# PANUmbRev2.net
KiCad netlist of a schematic drawn in Altium Designer
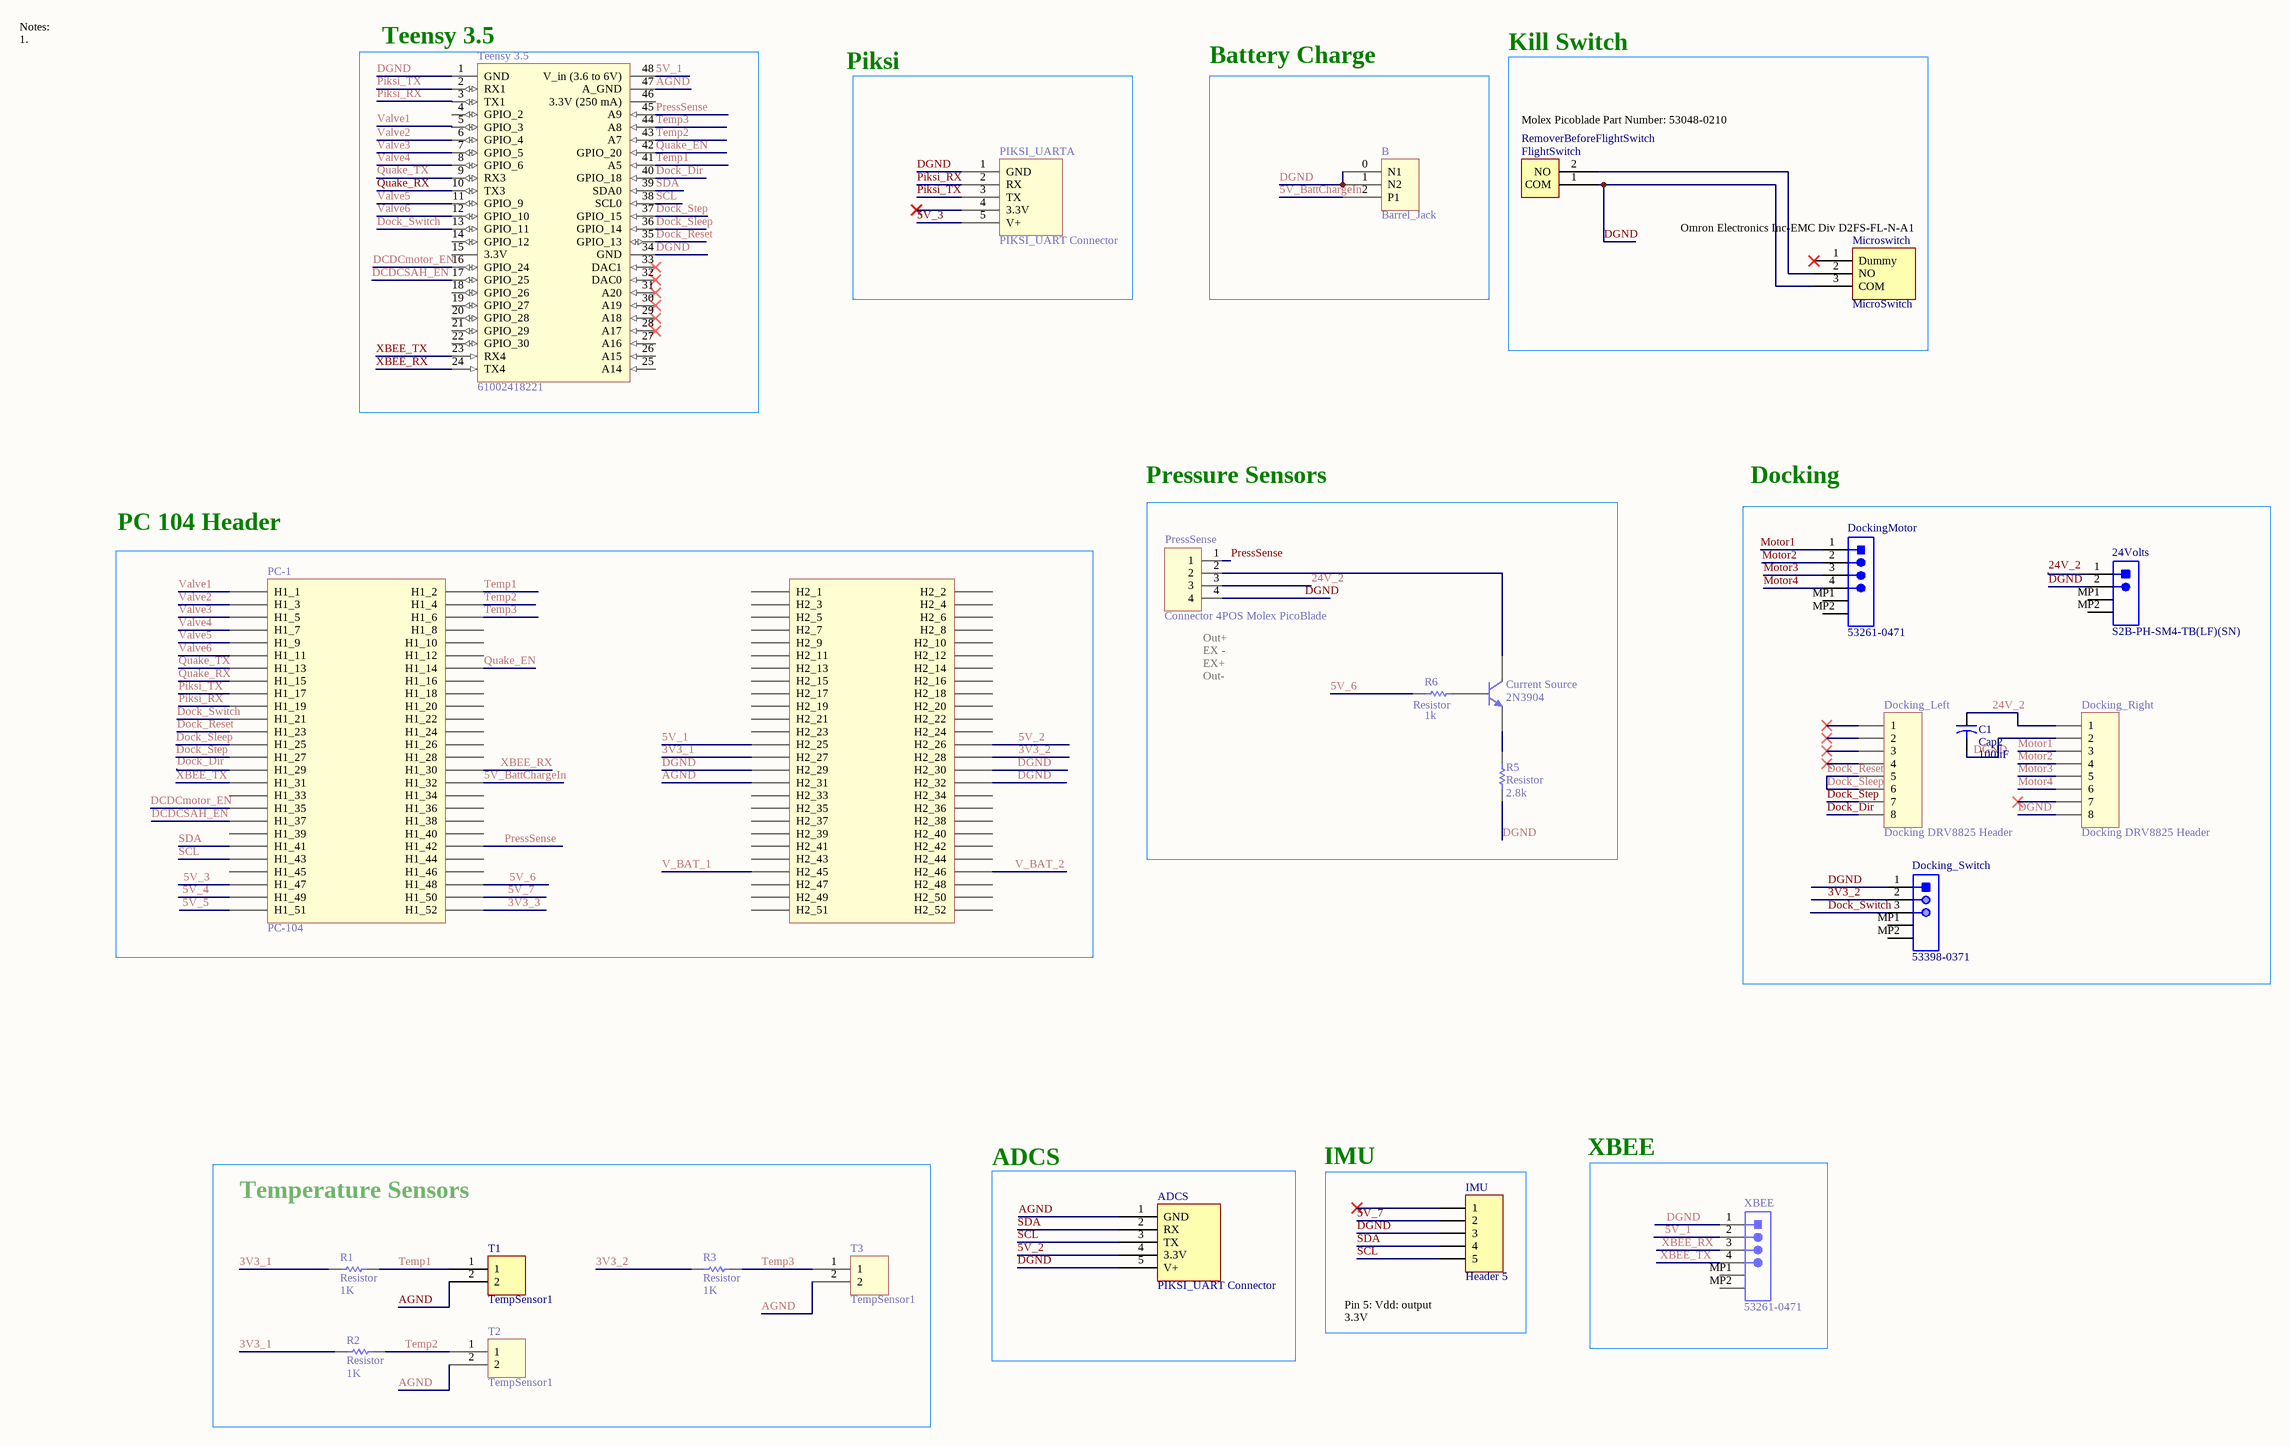
[diagram p0: PANUmbRev2.SchDoc]

(export (version "E")
  (design (tool "Eeschema 10.0.6"))
  (components
    (comp (ref "24Volts")
      (value "S2B-PH-SM4-TB(LF)(SN)")
      (footprint "JST- S2B-PH-SM4-TB(LF)(SN)-2_V")
      (description "Male Header, Pitch 2 mm, 1 x 2 Position, Height 5.5 mm, -25 to 85 degC, RoHS, Tape and Reel")
      (libsource (lib "Altium Content Vault") (part "CN-1P-2M-R2"))
    )
    (comp (ref "ADCS")
      (value "PIKSI_UART Connector")
      (footprint "UmbilicalConnectors:Molex Picoblade 5 Pin")
      (description "Molex Picoblade 53261-0571")
      (libsource (lib "UmbilicalBoardV2") (part "PIKSI_UART Connector"))
    )
    (comp (ref "B")
      (value "Barrel_Jack")
      (footprint "UmbilicalConnectors:Barrel_Jack")
      (libsource (lib "UmbilicalBoardV2") (part "Barrel_Jack"))
    )
    (comp (ref "C1")
      (value "Cap2")
      (footprint "CAPR5-4X5")
      (description "Capacitor")
      (fields (field (name "ALTIUM_VALUE") "100uF") (field (name "PUBLISHER") "Altium Limited"))
      (libsource (lib "Miscellaneous Devices") (part "Cap2"))
    )
    (comp (ref "Current Source")
      (value "2N3904")
      (footprint "TO-92A")
      (description "NPN General Purpose Amplifier")
      (fields (field (name "PUBLISHER") "Altium Limited"))
      (libsource (lib "Miscellaneous Devices") (part "2N3904"))
    )
    (comp (ref "DockingMotor")
      (value "53261-0471")
      (footprint "MOLEX-53261-0471_V")
      (description "Male Header, Pitch 1.25 mm, 1 x 4 Position, Height 3.4 mm, -40 to 85 degC, RoHS, Tape and Reel")
      (fields (field (name "MANUFACTURER") "Molex"))
      (libsource (lib "Altium Content Vault") (part "CN-1P-2M-R4_A"))
    )
    (comp (ref "Docking_Left")
      (value "Docking DRV8825 Header")
      (footprint "HDR1X8")
      (description "Header, 8-Pin")
      (fields (field (name "PUBLISHER") "Altium Limited"))
      (libsource (lib "Miscellaneous Connectors") (part "Header 8"))
    )
    (comp (ref "Docking_Right")
      (value "Docking DRV8825 Header")
      (footprint "HDR1X8")
      (description "Header, 8-Pin")
      (fields (field (name "PUBLISHER") "Altium Limited"))
      (libsource (lib "Miscellaneous Connectors") (part "Header 8"))
    )
    (comp (ref "Docking_Switch")
      (value "53398-0371")
      (footprint "MOLX-53398-0371_V")
      (description "Male Header, Pitch 1.25 mm, 1 x 3 Position, Height 4.7 mm, -40 to 85 degC, RoHS, Tape and Reel")
      (fields (field (name "MANUFACTURER") "Molex"))
      (libsource (lib "Altium Content Vault") (part "CN-1P-2M-R3"))
    )
    (comp (ref "FlightSwitch")
      (value "RemoverBeforeFlightSwitch")
      (footprint "UmbilicalConnectors:RemoverBeforeFlight Switch")
      (description "53048-0210 Molex Picoblade")
      (libsource (lib "") (part "RemoverBeforeFlightSwitch_1"))
    )
    (comp (ref "IMU")
      (value "Header 5")
      (footprint "HDR1X5")
      (description "Header, 5-Pin")
      (fields (field (name "PUBLISHER") "Altium Limited"))
      (libsource (lib "Miscellaneous Connectors") (part "Header 5"))
    )
    (comp (ref "Microswitch")
      (value "MicroSwitch")
      (footprint "UmbilicalConnectors:MicroSwitch_3pin")
      (description "Omron Electronics Inc-EMC Div D2FS-FL-N-A1")
      (libsource (lib "UmbilicalBoardV2") (part "MicroSwitch"))
    )
    (comp (ref "PC-1")
      (value "PC-104")
      (footprint "PC-104FOOTPRINT")
      (description "ESQ-126-14-G-D (2 total needed)")
      (libsource (lib "AdapterBoard") (part "PC-104"))
    )
    (comp (ref "PIKSI_UARTA")
      (value "PIKSI_UART Connector")
      (footprint "UmbilicalConnectors:Molex Picoblade 5 Pin")
      (description "Molex Picoblade 53261-0571")
      (libsource (lib "UmbilicalBoardV2") (part "PIKSI_UART Connector"))
    )
    (comp (ref "PressSense")
      (value "Connector 4POS Molex PicoBlade")
      (footprint "532610471")
      (libsource (lib "SchematicComponents") (part "532610471"))
    )
    (comp (ref "R1")
      (value "Resistor")
      (footprint "AXIAL-0.3")
      (fields (field (name "ALTIUM_VALUE") "1K") (field (name "PUBLISHER") "Altium Limited"))
      (libsource (lib "Miscellaneous Devices") (part "Res1"))
    )
    (comp (ref "R2")
      (value "Resistor")
      (footprint "AXIAL-0.3")
      (fields (field (name "ALTIUM_VALUE") "1K") (field (name "PUBLISHER") "Altium Limited"))
      (libsource (lib "Miscellaneous Devices") (part "Res1"))
    )
    (comp (ref "R3")
      (value "Resistor")
      (footprint "AXIAL-0.3")
      (fields (field (name "ALTIUM_VALUE") "1K") (field (name "PUBLISHER") "Altium Limited"))
      (libsource (lib "Miscellaneous Devices") (part "Res1"))
    )
    (comp (ref "R5")
      (value "Resistor")
      (footprint "AXIAL-0.3")
      (fields (field (name "ALTIUM_VALUE") "2.8k") (field (name "PUBLISHER") "Altium Limited"))
      (libsource (lib "Miscellaneous Devices") (part "Res1"))
    )
    (comp (ref "R6")
      (value "Resistor")
      (footprint "AXIAL-0.3")
      (fields (field (name "ALTIUM_VALUE") "1k") (field (name "PUBLISHER") "Altium Limited"))
      (libsource (lib "Miscellaneous Devices") (part "Res1"))
    )
    (comp (ref "T1")
      (value "TempSensor1")
      (footprint "UmbilicalConnectors:RemoverBeforeFlight Switch")
      (description "53048-0210 Molex Picoblade")
      (libsource (lib "UmbilicalBoardV2") (part "RemoverBeforeFlightSwitch"))
    )
    (comp (ref "T2")
      (value "TempSensor1")
      (footprint "UmbilicalConnectors:RemoverBeforeFlight Switch")
      (description "53048-0210 Molex Picoblade")
      (libsource (lib "UmbilicalBoardV2") (part "RemoverBeforeFlightSwitch"))
    )
    (comp (ref "T3")
      (value "TempSensor1")
      (footprint "UmbilicalConnectors:RemoverBeforeFlight Switch")
      (description "53048-0210 Molex Picoblade")
      (libsource (lib "UmbilicalBoardV2") (part "RemoverBeforeFlightSwitch"))
    )
    (comp (ref "Teensy 3.5")
      (value "61002418221")
      (footprint "61002418221")
      (fields (field (name "RS PART NUMBER") "1216841"))
      (libsource (lib "Teensy 3-5 24POS 2ROW SMD") (part "61002418221"))
    )
    (comp (ref "XBEE")
      (value "53261-0471")
      (footprint "MOLEX-53261-0471_V")
      (description "Male Header, Pitch 1.25 mm, 1 x 4 Position, Height 3.4 mm, -40 to 85 degC, RoHS, Tape and Reel")
      (fields (field (name "MANUFACTURER") "Molex"))
      (libsource (lib "Altium Content Vault") (part "CMP-2000-05238-1"))
    )
  )
  (nets
    (net (code "1") (name "/3V3_1") (class "Default")
      (node (ref "PC-1") (pin "H2_27") (pinfunction "H2_27_H2_27") (pintype "passive"))
      (node (ref "R1") (pin "1") (pinfunction "1_1") (pintype "passive"))
      (node (ref "R2") (pin "1") (pinfunction "1_1") (pintype "passive"))
    )
    (net (code "2") (name "/3V3_2") (class "Default")
      (node (ref "Docking_Switch") (pin "2") (pinfunction "2_2") (pintype "passive"))
      (node (ref "PC-1") (pin "H2_28") (pinfunction "H2_28_H2_28") (pintype "passive"))
      (node (ref "R3") (pin "1") (pinfunction "1_1") (pintype "passive"))
    )
    (net (code "3") (name "/3V3_3") (class "Default")
      (node (ref "PC-1") (pin "H1_52") (pinfunction "H1_52_H1_52") (pintype "passive"))
    )
    (net (code "4") (name "/5V_1") (class "Default")
      (node (ref "PC-1") (pin "H2_25") (pinfunction "H2_25_H2_25") (pintype "passive"))
      (node (ref "Teensy 3.5") (pin "48") (pinfunction "V_in_(3.6_to_6V)_48") (pintype "power_in"))
      (node (ref "XBEE") (pin "2") (pinfunction "2_2") (pintype "passive"))
    )
    (net (code "5") (name "/5V_2") (class "Default")
      (node (ref "ADCS") (pin "4") (pinfunction "3.3V_4") (pintype "passive"))
      (node (ref "PC-1") (pin "H2_26") (pinfunction "H2_26_H2_26") (pintype "passive"))
    )
    (net (code "6") (name "/5V_3") (class "Default")
      (node (ref "PC-1") (pin "H1_47") (pinfunction "H1_47_H1_47") (pintype "passive"))
      (node (ref "PIKSI_UARTA") (pin "5") (pinfunction "V+_5") (pintype "passive"))
    )
    (net (code "7") (name "/5V_4") (class "Default")
      (node (ref "PC-1") (pin "H1_49") (pinfunction "H1_49_H1_49") (pintype "passive"))
    )
    (net (code "8") (name "/5V_5") (class "Default")
      (node (ref "PC-1") (pin "H1_51") (pinfunction "H1_51_H1_51") (pintype "passive"))
    )
    (net (code "9") (name "/5V_6") (class "Default")
      (node (ref "PC-1") (pin "H1_48") (pinfunction "H1_48_H1_48") (pintype "passive"))
      (node (ref "R6") (pin "2") (pinfunction "2_2") (pintype "passive"))
    )
    (net (code "10") (name "/5V_7") (class "Default")
      (node (ref "IMU") (pin "2") (pinfunction "2_2") (pintype "passive"))
      (node (ref "PC-1") (pin "H1_50") (pinfunction "H1_50_H1_50") (pintype "passive"))
    )
    (net (code "11") (name "/5V_BattChargeIn") (class "Default")
      (node (ref "B") (pin "2") (pinfunction "P1_2") (pintype "passive"))
      (node (ref "PC-1") (pin "H1_32") (pinfunction "H1_32_H1_32") (pintype "passive"))
    )
    (net (code "12") (name "/24V_2") (class "Default")
      (node (ref "24Volts") (pin "1") (pinfunction "1_1") (pintype "passive"))
      (node (ref "C1") (pin "1") (pinfunction "1_1") (pintype "passive"))
      (node (ref "Docking_Right") (pin "1") (pinfunction "1_1") (pintype "passive"))
      (node (ref "PressSense") (pin "3") (pinfunction "3_3") (pintype "passive"))
    )
    (net (code "13") (name "/AGND") (class "Default")
      (node (ref "ADCS") (pin "1") (pinfunction "GND_1") (pintype "passive"))
      (node (ref "PC-1") (pin "H2_31") (pinfunction "H2_31_H2_31") (pintype "passive"))
      (node (ref "T1") (pin "2") (pinfunction "2_2") (pintype "passive"))
      (node (ref "T2") (pin "2") (pinfunction "2_2") (pintype "passive"))
      (node (ref "T3") (pin "2") (pinfunction "2_2") (pintype "passive"))
      (node (ref "Teensy 3.5") (pin "47") (pinfunction "A_GND_47") (pintype "power_in"))
    )
    (net (code "14") (name "/DCDCSAH_EN") (class "Default")
      (node (ref "PC-1") (pin "H1_37") (pinfunction "H1_37_H1_37") (pintype "passive"))
      (node (ref "Teensy 3.5") (pin "17") (pinfunction "GPIO_25_17") (pintype "bidirectional"))
    )
    (net (code "15") (name "/DCDCmotor_EN") (class "Default")
      (node (ref "PC-1") (pin "H1_35") (pinfunction "H1_35_H1_35") (pintype "passive"))
      (node (ref "Teensy 3.5") (pin "16") (pinfunction "GPIO_24_16") (pintype "bidirectional"))
    )
    (net (code "16") (name "/DGND") (class "Default")
      (node (ref "24Volts") (pin "2") (pinfunction "2_2") (pintype "passive"))
      (node (ref "ADCS") (pin "5") (pinfunction "V+_5") (pintype "passive"))
      (node (ref "B") (pin "0") (pinfunction "N1_0") (pintype "passive"))
      (node (ref "B") (pin "1") (pinfunction "N2_1") (pintype "passive"))
      (node (ref "C1") (pin "2") (pinfunction "2_2") (pintype "passive"))
      (node (ref "Docking_Right") (pin "2") (pinfunction "2_2") (pintype "passive"))
      (node (ref "Docking_Right") (pin "8") (pinfunction "8_8") (pintype "passive"))
      (node (ref "Docking_Switch") (pin "1") (pinfunction "1_1") (pintype "passive"))
      (node (ref "FlightSwitch") (pin "1") (pinfunction "COM_1") (pintype "passive"))
      (node (ref "IMU") (pin "3") (pinfunction "3_3") (pintype "passive"))
      (node (ref "Microswitch") (pin "3") (pinfunction "COM_3") (pintype "passive"))
      (node (ref "PC-1") (pin "H2_29") (pinfunction "H2_29_H2_29") (pintype "passive"))
      (node (ref "PC-1") (pin "H2_30") (pinfunction "H2_30_H2_30") (pintype "passive"))
      (node (ref "PC-1") (pin "H2_32") (pinfunction "H2_32_H2_32") (pintype "passive"))
      (node (ref "PIKSI_UARTA") (pin "1") (pinfunction "GND_1") (pintype "passive"))
      (node (ref "PressSense") (pin "4") (pinfunction "4_4") (pintype "passive"))
      (node (ref "R5") (pin "1") (pinfunction "1_1") (pintype "passive"))
      (node (ref "Teensy 3.5") (pin "1") (pinfunction "GND_1") (pintype "power_in"))
      (node (ref "Teensy 3.5") (pin "34") (pinfunction "GND_34") (pintype "power_in"))
      (node (ref "XBEE") (pin "1") (pinfunction "1_1") (pintype "passive"))
    )
    (net (code "17") (name "/Dock_Dir") (class "Default")
      (node (ref "Docking_Left") (pin "8") (pinfunction "8_8") (pintype "passive"))
      (node (ref "PC-1") (pin "H1_29") (pinfunction "H1_29_H1_29") (pintype "passive"))
      (node (ref "Teensy 3.5") (pin "40") (pinfunction "GPIO_18_40") (pintype "input"))
    )
    (net (code "18") (name "/Dock_Reset") (class "Default")
      (node (ref "Docking_Left") (pin "5") (pinfunction "5_5") (pintype "passive"))
      (node (ref "Docking_Left") (pin "6") (pinfunction "6_6") (pintype "passive"))
      (node (ref "PC-1") (pin "H1_23") (pinfunction "H1_23_H1_23") (pintype "passive"))
      (node (ref "PC-1") (pin "H1_25") (pinfunction "H1_25_H1_25") (pintype "passive"))
      (node (ref "Teensy 3.5") (pin "35") (pinfunction "GPIO_13_35") (pintype "bidirectional"))
      (node (ref "Teensy 3.5") (pin "36") (pinfunction "GPIO_14_36") (pintype "input"))
    )
    (net (code "19") (name "/Dock_Step") (class "Default")
      (node (ref "Docking_Left") (pin "7") (pinfunction "7_7") (pintype "passive"))
      (node (ref "PC-1") (pin "H1_27") (pinfunction "H1_27_H1_27") (pintype "passive"))
      (node (ref "Teensy 3.5") (pin "37") (pinfunction "GPIO_15_37") (pintype "input"))
    )
    (net (code "20") (name "/Dock_Switch") (class "Default")
      (node (ref "Docking_Switch") (pin "3") (pinfunction "3_3") (pintype "passive"))
      (node (ref "PC-1") (pin "H1_21") (pinfunction "H1_21_H1_21") (pintype "passive"))
      (node (ref "Teensy 3.5") (pin "13") (pinfunction "GPIO_11_13") (pintype "bidirectional"))
    )
    (net (code "21") (name "/Motor1") (class "Default")
      (node (ref "DockingMotor") (pin "1") (pinfunction "1_1") (pintype "passive"))
      (node (ref "Docking_Right") (pin "3") (pinfunction "3_3") (pintype "passive"))
    )
    (net (code "22") (name "/Motor2") (class "Default")
      (node (ref "DockingMotor") (pin "2") (pinfunction "2_2") (pintype "passive"))
      (node (ref "Docking_Right") (pin "4") (pinfunction "4_4") (pintype "passive"))
    )
    (net (code "23") (name "/Motor3") (class "Default")
      (node (ref "DockingMotor") (pin "3") (pinfunction "3_3") (pintype "passive"))
      (node (ref "Docking_Right") (pin "5") (pinfunction "5_5") (pintype "passive"))
    )
    (net (code "24") (name "/Motor4") (class "Default")
      (node (ref "DockingMotor") (pin "4") (pinfunction "4_4") (pintype "passive"))
      (node (ref "Docking_Right") (pin "6") (pinfunction "6_6") (pintype "passive"))
    )
    (net (code "25") (name "/Piksi_RX") (class "Default")
      (node (ref "PC-1") (pin "H1_19") (pinfunction "H1_19_H1_19") (pintype "passive"))
      (node (ref "PIKSI_UARTA") (pin "2") (pinfunction "RX_2") (pintype "passive"))
      (node (ref "Teensy 3.5") (pin "3") (pinfunction "TX1_3") (pintype "bidirectional"))
    )
    (net (code "26") (name "/Piksi_TX") (class "Default")
      (node (ref "PC-1") (pin "H1_17") (pinfunction "H1_17_H1_17") (pintype "passive"))
      (node (ref "PIKSI_UARTA") (pin "3") (pinfunction "TX_3") (pintype "passive"))
      (node (ref "Teensy 3.5") (pin "2") (pinfunction "RX1_2") (pintype "bidirectional"))
    )
    (net (code "27") (name "/PressSense") (class "Default")
      (node (ref "PC-1") (pin "H1_42") (pinfunction "H1_42_H1_42") (pintype "passive"))
      (node (ref "PressSense") (pin "1") (pinfunction "1_1") (pintype "passive"))
      (node (ref "Teensy 3.5") (pin "45") (pinfunction "A9_45") (pintype "input"))
    )
    (net (code "28") (name "/Quake_EN") (class "Default")
      (node (ref "PC-1") (pin "H1_14") (pinfunction "H1_14_H1_14") (pintype "passive"))
      (node (ref "Teensy 3.5") (pin "42") (pinfunction "GPIO_20_42") (pintype "input"))
    )
    (net (code "29") (name "/Quake_RX") (class "Default")
      (node (ref "PC-1") (pin "H1_15") (pinfunction "H1_15_H1_15") (pintype "passive"))
      (node (ref "Teensy 3.5") (pin "10") (pinfunction "TX3_10") (pintype "bidirectional"))
    )
    (net (code "30") (name "/Quake_TX") (class "Default")
      (node (ref "PC-1") (pin "H1_13") (pinfunction "H1_13_H1_13") (pintype "passive"))
      (node (ref "Teensy 3.5") (pin "9") (pinfunction "RX3_9") (pintype "bidirectional"))
    )
    (net (code "31") (name "/SCL") (class "Default")
      (node (ref "ADCS") (pin "3") (pinfunction "TX_3") (pintype "passive"))
      (node (ref "IMU") (pin "5") (pinfunction "5_5") (pintype "passive"))
      (node (ref "PC-1") (pin "H1_43") (pinfunction "H1_43_H1_43") (pintype "passive"))
      (node (ref "Teensy 3.5") (pin "38") (pinfunction "SCL0_38") (pintype "input"))
    )
    (net (code "32") (name "/SDA") (class "Default")
      (node (ref "ADCS") (pin "2") (pinfunction "RX_2") (pintype "passive"))
      (node (ref "IMU") (pin "4") (pinfunction "4_4") (pintype "passive"))
      (node (ref "PC-1") (pin "H1_41") (pinfunction "H1_41_H1_41") (pintype "passive"))
      (node (ref "Teensy 3.5") (pin "39") (pinfunction "SDA0_39") (pintype "input"))
    )
    (net (code "33") (name "/Temp1") (class "Default")
      (node (ref "PC-1") (pin "H1_2") (pinfunction "H1_2_H1_2") (pintype "passive"))
      (node (ref "R1") (pin "2") (pinfunction "2_2") (pintype "passive"))
      (node (ref "T1") (pin "1") (pinfunction "1_1") (pintype "passive"))
      (node (ref "Teensy 3.5") (pin "41") (pinfunction "A5_41") (pintype "input"))
    )
    (net (code "34") (name "/Temp2") (class "Default")
      (node (ref "PC-1") (pin "H1_4") (pinfunction "H1_4_H1_4") (pintype "passive"))
      (node (ref "R2") (pin "2") (pinfunction "2_2") (pintype "passive"))
      (node (ref "T2") (pin "1") (pinfunction "1_1") (pintype "passive"))
      (node (ref "Teensy 3.5") (pin "43") (pinfunction "A7_43") (pintype "input"))
    )
    (net (code "35") (name "/Temp3") (class "Default")
      (node (ref "PC-1") (pin "H1_6") (pinfunction "H1_6_H1_6") (pintype "passive"))
      (node (ref "R3") (pin "2") (pinfunction "2_2") (pintype "passive"))
      (node (ref "T3") (pin "1") (pinfunction "1_1") (pintype "passive"))
      (node (ref "Teensy 3.5") (pin "44") (pinfunction "A8_44") (pintype "input"))
    )
    (net (code "36") (name "/V_BAT_1") (class "Default")
      (node (ref "PC-1") (pin "H2_45") (pinfunction "H2_45_H2_45") (pintype "passive"))
    )
    (net (code "37") (name "/V_BAT_2") (class "Default")
      (node (ref "PC-1") (pin "H2_46") (pinfunction "H2_46_H2_46") (pintype "passive"))
    )
    (net (code "38") (name "/Valve1") (class "Default")
      (node (ref "PC-1") (pin "H1_1") (pinfunction "H1_1_H1_1") (pintype "passive"))
      (node (ref "Teensy 3.5") (pin "5") (pinfunction "GPIO_3_5") (pintype "bidirectional"))
    )
    (net (code "39") (name "/Valve2") (class "Default")
      (node (ref "PC-1") (pin "H1_3") (pinfunction "H1_3_H1_3") (pintype "passive"))
      (node (ref "Teensy 3.5") (pin "6") (pinfunction "GPIO_4_6") (pintype "bidirectional"))
    )
    (net (code "40") (name "/Valve3") (class "Default")
      (node (ref "PC-1") (pin "H1_5") (pinfunction "H1_5_H1_5") (pintype "passive"))
      (node (ref "Teensy 3.5") (pin "7") (pinfunction "GPIO_5_7") (pintype "bidirectional"))
    )
    (net (code "41") (name "/Valve4") (class "Default")
      (node (ref "PC-1") (pin "H1_7") (pinfunction "H1_7_H1_7") (pintype "passive"))
      (node (ref "Teensy 3.5") (pin "8") (pinfunction "GPIO_6_8") (pintype "bidirectional"))
    )
    (net (code "42") (name "/Valve5") (class "Default")
      (node (ref "PC-1") (pin "H1_9") (pinfunction "H1_9_H1_9") (pintype "passive"))
      (node (ref "Teensy 3.5") (pin "11") (pinfunction "GPIO_9_11") (pintype "bidirectional"))
    )
    (net (code "43") (name "/Valve6") (class "Default")
      (node (ref "PC-1") (pin "H1_11") (pinfunction "H1_11_H1_11") (pintype "passive"))
      (node (ref "Teensy 3.5") (pin "12") (pinfunction "GPIO_10_12") (pintype "bidirectional"))
    )
    (net (code "44") (name "/XBEE_RX") (class "Default")
      (node (ref "PC-1") (pin "H1_30") (pinfunction "H1_30_H1_30") (pintype "passive"))
      (node (ref "Teensy 3.5") (pin "24") (pinfunction "TX4_24") (pintype "input"))
      (node (ref "XBEE") (pin "3") (pinfunction "3_3") (pintype "passive"))
    )
    (net (code "45") (name "/XBEE_TX") (class "Default")
      (node (ref "PC-1") (pin "H1_31") (pinfunction "H1_31_H1_31") (pintype "passive"))
      (node (ref "Teensy 3.5") (pin "23") (pinfunction "RX4_23") (pintype "input"))
      (node (ref "XBEE") (pin "4") (pinfunction "4_4") (pintype "passive"))
    )
    (net (code "46") (name "Net-(Current Source-B)") (class "Default")
      (node (ref "Current Source") (pin "2") (pinfunction "B_2") (pintype "passive"))
      (node (ref "R6") (pin "1") (pinfunction "1_1") (pintype "passive"))
    )
    (net (code "47") (name "Net-(Current Source-C)") (class "Default")
      (node (ref "Current Source") (pin "3") (pinfunction "C_3") (pintype "passive"))
      (node (ref "PressSense") (pin "2") (pinfunction "2_2") (pintype "passive"))
    )
    (net (code "48") (name "Net-(Current Source-E)") (class "Default")
      (node (ref "Current Source") (pin "1") (pinfunction "E_1") (pintype "passive"))
      (node (ref "R5") (pin "2") (pinfunction "2_2") (pintype "passive"))
    )
    (net (code "49") (name "Net-(FlightSwitch-NO)") (class "Default")
      (node (ref "FlightSwitch") (pin "2") (pinfunction "NO_2") (pintype "passive"))
      (node (ref "Microswitch") (pin "2") (pinfunction "NO_2") (pintype "passive"))
    )
    (net (code "50") (name "unconnected-(24Volts-PadMP1)") (class "Default")
      (node (ref "24Volts") (pin "MP1") (pinfunction "MP1_MP1") (pintype "passive"))
    )
    (net (code "51") (name "unconnected-(24Volts-PadMP2)") (class "Default")
      (node (ref "24Volts") (pin "MP2") (pinfunction "MP2_MP2") (pintype "passive"))
    )
    (net (code "52") (name "unconnected-(DockingMotor-PadMP1)") (class "Default")
      (node (ref "DockingMotor") (pin "MP1") (pinfunction "MP1_MP1") (pintype "passive"))
    )
    (net (code "53") (name "unconnected-(DockingMotor-PadMP2)") (class "Default")
      (node (ref "DockingMotor") (pin "MP2") (pinfunction "MP2_MP2") (pintype "passive"))
    )
    (net (code "54") (name "unconnected-(Docking_Left-Pad1)") (class "Default")
      (node (ref "Docking_Left") (pin "1") (pinfunction "1_1") (pintype "passive+no_connect"))
    )
    (net (code "55") (name "unconnected-(Docking_Left-Pad2)") (class "Default")
      (node (ref "Docking_Left") (pin "2") (pinfunction "2_2") (pintype "passive+no_connect"))
    )
    (net (code "56") (name "unconnected-(Docking_Left-Pad3)") (class "Default")
      (node (ref "Docking_Left") (pin "3") (pinfunction "3_3") (pintype "passive+no_connect"))
    )
    (net (code "57") (name "unconnected-(Docking_Left-Pad4)") (class "Default")
      (node (ref "Docking_Left") (pin "4") (pinfunction "4_4") (pintype "passive+no_connect"))
    )
    (net (code "58") (name "unconnected-(Docking_Right-Pad7)") (class "Default")
      (node (ref "Docking_Right") (pin "7") (pinfunction "7_7") (pintype "passive+no_connect"))
    )
    (net (code "59") (name "unconnected-(Docking_Switch-PadMP1)") (class "Default")
      (node (ref "Docking_Switch") (pin "MP1") (pinfunction "MP1_MP1") (pintype "passive"))
    )
    (net (code "60") (name "unconnected-(Docking_Switch-PadMP2)") (class "Default")
      (node (ref "Docking_Switch") (pin "MP2") (pinfunction "MP2_MP2") (pintype "passive"))
    )
    (net (code "61") (name "unconnected-(IMU-Pad1)") (class "Default")
      (node (ref "IMU") (pin "1") (pinfunction "1_1") (pintype "passive+no_connect"))
    )
    (net (code "62") (name "unconnected-(Microswitch-Dummy-Pad1)") (class "Default")
      (node (ref "Microswitch") (pin "1") (pinfunction "Dummy_1") (pintype "passive+no_connect"))
    )
    (net (code "63") (name "unconnected-(PC-1-PadH1_8)") (class "Default")
      (node (ref "PC-1") (pin "H1_8") (pinfunction "H1_8_H1_8") (pintype "passive"))
    )
    (net (code "64") (name "unconnected-(PC-1-PadH1_10)") (class "Default")
      (node (ref "PC-1") (pin "H1_10") (pinfunction "H1_10_H1_10") (pintype "passive"))
    )
    (net (code "65") (name "unconnected-(PC-1-PadH1_12)") (class "Default")
      (node (ref "PC-1") (pin "H1_12") (pinfunction "H1_12_H1_12") (pintype "passive"))
    )
    (net (code "66") (name "unconnected-(PC-1-PadH1_16)") (class "Default")
      (node (ref "PC-1") (pin "H1_16") (pinfunction "H1_16_H1_16") (pintype "passive"))
    )
    (net (code "67") (name "unconnected-(PC-1-PadH1_18)") (class "Default")
      (node (ref "PC-1") (pin "H1_18") (pinfunction "H1_18_H1_18") (pintype "passive"))
    )
    (net (code "68") (name "unconnected-(PC-1-PadH1_20)") (class "Default")
      (node (ref "PC-1") (pin "H1_20") (pinfunction "H1_20_H1_20") (pintype "passive"))
    )
    (net (code "69") (name "unconnected-(PC-1-PadH1_22)") (class "Default")
      (node (ref "PC-1") (pin "H1_22") (pinfunction "H1_22_H1_22") (pintype "passive"))
    )
    (net (code "70") (name "unconnected-(PC-1-PadH1_24)") (class "Default")
      (node (ref "PC-1") (pin "H1_24") (pinfunction "H1_24_H1_24") (pintype "passive"))
    )
    (net (code "71") (name "unconnected-(PC-1-PadH1_26)") (class "Default")
      (node (ref "PC-1") (pin "H1_26") (pinfunction "H1_26_H1_26") (pintype "passive"))
    )
    (net (code "72") (name "unconnected-(PC-1-PadH1_28)") (class "Default")
      (node (ref "PC-1") (pin "H1_28") (pinfunction "H1_28_H1_28") (pintype "passive"))
    )
    (net (code "73") (name "unconnected-(PC-1-PadH1_33)") (class "Default")
      (node (ref "PC-1") (pin "H1_33") (pinfunction "H1_33_H1_33") (pintype "passive"))
    )
    (net (code "74") (name "unconnected-(PC-1-PadH1_34)") (class "Default")
      (node (ref "PC-1") (pin "H1_34") (pinfunction "H1_34_H1_34") (pintype "passive"))
    )
    (net (code "75") (name "unconnected-(PC-1-PadH1_36)") (class "Default")
      (node (ref "PC-1") (pin "H1_36") (pinfunction "H1_36_H1_36") (pintype "passive"))
    )
    (net (code "76") (name "unconnected-(PC-1-PadH1_38)") (class "Default")
      (node (ref "PC-1") (pin "H1_38") (pinfunction "H1_38_H1_38") (pintype "passive"))
    )
    (net (code "77") (name "unconnected-(PC-1-PadH1_39)") (class "Default")
      (node (ref "PC-1") (pin "H1_39") (pinfunction "H1_39_H1_39") (pintype "passive"))
    )
    (net (code "78") (name "unconnected-(PC-1-PadH1_40)") (class "Default")
      (node (ref "PC-1") (pin "H1_40") (pinfunction "H1_40_H1_40") (pintype "passive"))
    )
    (net (code "79") (name "unconnected-(PC-1-PadH1_44)") (class "Default")
      (node (ref "PC-1") (pin "H1_44") (pinfunction "H1_44_H1_44") (pintype "passive"))
    )
    (net (code "80") (name "unconnected-(PC-1-PadH1_45)") (class "Default")
      (node (ref "PC-1") (pin "H1_45") (pinfunction "H1_45_H1_45") (pintype "passive"))
    )
    (net (code "81") (name "unconnected-(PC-1-PadH1_46)") (class "Default")
      (node (ref "PC-1") (pin "H1_46") (pinfunction "H1_46_H1_46") (pintype "passive"))
    )
    (net (code "82") (name "unconnected-(PC-1-PadH2_1)") (class "Default")
      (node (ref "PC-1") (pin "H2_1") (pinfunction "H2_1_H2_1") (pintype "passive"))
    )
    (net (code "83") (name "unconnected-(PC-1-PadH2_2)") (class "Default")
      (node (ref "PC-1") (pin "H2_2") (pinfunction "H2_2_H2_2") (pintype "passive"))
    )
    (net (code "84") (name "unconnected-(PC-1-PadH2_3)") (class "Default")
      (node (ref "PC-1") (pin "H2_3") (pinfunction "H2_3_H2_3") (pintype "passive"))
    )
    (net (code "85") (name "unconnected-(PC-1-PadH2_4)") (class "Default")
      (node (ref "PC-1") (pin "H2_4") (pinfunction "H2_4_H2_4") (pintype "passive"))
    )
    (net (code "86") (name "unconnected-(PC-1-PadH2_5)") (class "Default")
      (node (ref "PC-1") (pin "H2_5") (pinfunction "H2_5_H2_5") (pintype "passive"))
    )
    (net (code "87") (name "unconnected-(PC-1-PadH2_6)") (class "Default")
      (node (ref "PC-1") (pin "H2_6") (pinfunction "H2_6_H2_6") (pintype "passive"))
    )
    (net (code "88") (name "unconnected-(PC-1-PadH2_7)") (class "Default")
      (node (ref "PC-1") (pin "H2_7") (pinfunction "H2_7_H2_7") (pintype "passive"))
    )
    (net (code "89") (name "unconnected-(PC-1-PadH2_8)") (class "Default")
      (node (ref "PC-1") (pin "H2_8") (pinfunction "H2_8_H2_8") (pintype "passive"))
    )
    (net (code "90") (name "unconnected-(PC-1-PadH2_9)") (class "Default")
      (node (ref "PC-1") (pin "H2_9") (pinfunction "H2_9_H2_9") (pintype "passive"))
    )
    (net (code "91") (name "unconnected-(PC-1-PadH2_10)") (class "Default")
      (node (ref "PC-1") (pin "H2_10") (pinfunction "H2_10_H2_10") (pintype "passive"))
    )
    (net (code "92") (name "unconnected-(PC-1-PadH2_11)") (class "Default")
      (node (ref "PC-1") (pin "H2_11") (pinfunction "H2_11_H2_11") (pintype "passive"))
    )
    (net (code "93") (name "unconnected-(PC-1-PadH2_12)") (class "Default")
      (node (ref "PC-1") (pin "H2_12") (pinfunction "H2_12_H2_12") (pintype "passive"))
    )
    (net (code "94") (name "unconnected-(PC-1-PadH2_13)") (class "Default")
      (node (ref "PC-1") (pin "H2_13") (pinfunction "H2_13_H2_13") (pintype "passive"))
    )
    (net (code "95") (name "unconnected-(PC-1-PadH2_14)") (class "Default")
      (node (ref "PC-1") (pin "H2_14") (pinfunction "H2_14_H2_14") (pintype "passive"))
    )
    (net (code "96") (name "unconnected-(PC-1-PadH2_15)") (class "Default")
      (node (ref "PC-1") (pin "H2_15") (pinfunction "H2_15_H2_15") (pintype "passive"))
    )
    (net (code "97") (name "unconnected-(PC-1-PadH2_16)") (class "Default")
      (node (ref "PC-1") (pin "H2_16") (pinfunction "H2_16_H2_16") (pintype "passive"))
    )
    (net (code "98") (name "unconnected-(PC-1-PadH2_17)") (class "Default")
      (node (ref "PC-1") (pin "H2_17") (pinfunction "H2_17_H2_17") (pintype "passive"))
    )
    (net (code "99") (name "unconnected-(PC-1-PadH2_18)") (class "Default")
      (node (ref "PC-1") (pin "H2_18") (pinfunction "H2_18_H2_18") (pintype "passive"))
    )
    (net (code "100") (name "unconnected-(PC-1-PadH2_19)") (class "Default")
      (node (ref "PC-1") (pin "H2_19") (pinfunction "H2_19_H2_19") (pintype "passive"))
    )
    (net (code "101") (name "unconnected-(PC-1-PadH2_20)") (class "Default")
      (node (ref "PC-1") (pin "H2_20") (pinfunction "H2_20_H2_20") (pintype "passive"))
    )
    (net (code "102") (name "unconnected-(PC-1-PadH2_21)") (class "Default")
      (node (ref "PC-1") (pin "H2_21") (pinfunction "H2_21_H2_21") (pintype "passive"))
    )
    (net (code "103") (name "unconnected-(PC-1-PadH2_22)") (class "Default")
      (node (ref "PC-1") (pin "H2_22") (pinfunction "H2_22_H2_22") (pintype "passive"))
    )
    (net (code "104") (name "unconnected-(PC-1-PadH2_23)") (class "Default")
      (node (ref "PC-1") (pin "H2_23") (pinfunction "H2_23_H2_23") (pintype "passive"))
    )
    (net (code "105") (name "unconnected-(PC-1-PadH2_24)") (class "Default")
      (node (ref "PC-1") (pin "H2_24") (pinfunction "H2_24_H2_24") (pintype "passive"))
    )
    (net (code "106") (name "unconnected-(PC-1-PadH2_33)") (class "Default")
      (node (ref "PC-1") (pin "H2_33") (pinfunction "H2_33_H2_33") (pintype "passive"))
    )
    (net (code "107") (name "unconnected-(PC-1-PadH2_34)") (class "Default")
      (node (ref "PC-1") (pin "H2_34") (pinfunction "H2_34_H2_34") (pintype "passive"))
    )
    (net (code "108") (name "unconnected-(PC-1-PadH2_35)") (class "Default")
      (node (ref "PC-1") (pin "H2_35") (pinfunction "H2_35_H2_35") (pintype "passive"))
    )
    (net (code "109") (name "unconnected-(PC-1-PadH2_36)") (class "Default")
      (node (ref "PC-1") (pin "H2_36") (pinfunction "H2_36_H2_36") (pintype "passive"))
    )
    (net (code "110") (name "unconnected-(PC-1-PadH2_37)") (class "Default")
      (node (ref "PC-1") (pin "H2_37") (pinfunction "H2_37_H2_37") (pintype "passive"))
    )
    (net (code "111") (name "unconnected-(PC-1-PadH2_38)") (class "Default")
      (node (ref "PC-1") (pin "H2_38") (pinfunction "H2_38_H2_38") (pintype "passive"))
    )
    (net (code "112") (name "unconnected-(PC-1-PadH2_39)") (class "Default")
      (node (ref "PC-1") (pin "H2_39") (pinfunction "H2_39_H2_39") (pintype "passive"))
    )
    (net (code "113") (name "unconnected-(PC-1-PadH2_40)") (class "Default")
      (node (ref "PC-1") (pin "H2_40") (pinfunction "H2_40_H2_40") (pintype "passive"))
    )
    (net (code "114") (name "unconnected-(PC-1-PadH2_41)") (class "Default")
      (node (ref "PC-1") (pin "H2_41") (pinfunction "H2_41_H2_41") (pintype "passive"))
    )
    (net (code "115") (name "unconnected-(PC-1-PadH2_42)") (class "Default")
      (node (ref "PC-1") (pin "H2_42") (pinfunction "H2_42_H2_42") (pintype "passive"))
    )
    (net (code "116") (name "unconnected-(PC-1-PadH2_43)") (class "Default")
      (node (ref "PC-1") (pin "H2_43") (pinfunction "H2_43_H2_43") (pintype "passive"))
    )
    (net (code "117") (name "unconnected-(PC-1-PadH2_44)") (class "Default")
      (node (ref "PC-1") (pin "H2_44") (pinfunction "H2_44_H2_44") (pintype "passive"))
    )
    (net (code "118") (name "unconnected-(PC-1-PadH2_47)") (class "Default")
      (node (ref "PC-1") (pin "H2_47") (pinfunction "H2_47_H2_47") (pintype "passive"))
    )
    (net (code "119") (name "unconnected-(PC-1-PadH2_48)") (class "Default")
      (node (ref "PC-1") (pin "H2_48") (pinfunction "H2_48_H2_48") (pintype "passive"))
    )
    (net (code "120") (name "unconnected-(PC-1-PadH2_49)") (class "Default")
      (node (ref "PC-1") (pin "H2_49") (pinfunction "H2_49_H2_49") (pintype "passive"))
    )
    (net (code "121") (name "unconnected-(PC-1-PadH2_50)") (class "Default")
      (node (ref "PC-1") (pin "H2_50") (pinfunction "H2_50_H2_50") (pintype "passive"))
    )
    (net (code "122") (name "unconnected-(PC-1-PadH2_51)") (class "Default")
      (node (ref "PC-1") (pin "H2_51") (pinfunction "H2_51_H2_51") (pintype "passive"))
    )
    (net (code "123") (name "unconnected-(PC-1-PadH2_52)") (class "Default")
      (node (ref "PC-1") (pin "H2_52") (pinfunction "H2_52_H2_52") (pintype "passive"))
    )
    (net (code "124") (name "unconnected-(PIKSI_UARTA-3.3V-Pad4)") (class "Default")
      (node (ref "PIKSI_UARTA") (pin "4") (pinfunction "3.3V_4") (pintype "passive+no_connect"))
    )
    (net (code "125") (name "unconnected-(Teensy 3.5-3.3V-Pad15)") (class "Default")
      (node (ref "Teensy 3.5") (pin "15") (pinfunction "3.3V_15") (pintype "power_in"))
    )
    (net (code "126") (name "unconnected-(Teensy 3.5-3.3V_(250_mA)-Pad46)") (class "Default")
      (node (ref "Teensy 3.5") (pin "46") (pinfunction "3.3V_(250_mA)_46") (pintype "power_in"))
    )
    (net (code "127") (name "unconnected-(Teensy 3.5-A14-Pad25)") (class "Default")
      (node (ref "Teensy 3.5") (pin "25") (pinfunction "A14_25") (pintype "input"))
    )
    (net (code "128") (name "unconnected-(Teensy 3.5-A15-Pad26)") (class "Default")
      (node (ref "Teensy 3.5") (pin "26") (pinfunction "A15_26") (pintype "input"))
    )
    (net (code "129") (name "unconnected-(Teensy 3.5-A16-Pad27)") (class "Default")
      (node (ref "Teensy 3.5") (pin "27") (pinfunction "A16_27") (pintype "input"))
    )
    (net (code "130") (name "unconnected-(Teensy 3.5-A17-Pad28)") (class "Default")
      (node (ref "Teensy 3.5") (pin "28") (pinfunction "A17_28") (pintype "input+no_connect"))
    )
    (net (code "131") (name "unconnected-(Teensy 3.5-A18-Pad29)") (class "Default")
      (node (ref "Teensy 3.5") (pin "29") (pinfunction "A18_29") (pintype "input+no_connect"))
    )
    (net (code "132") (name "unconnected-(Teensy 3.5-A19-Pad30)") (class "Default")
      (node (ref "Teensy 3.5") (pin "30") (pinfunction "A19_30") (pintype "input+no_connect"))
    )
    (net (code "133") (name "unconnected-(Teensy 3.5-A20-Pad31)") (class "Default")
      (node (ref "Teensy 3.5") (pin "31") (pinfunction "A20_31") (pintype "input+no_connect"))
    )
    (net (code "134") (name "unconnected-(Teensy 3.5-DAC0-Pad32)") (class "Default")
      (node (ref "Teensy 3.5") (pin "32") (pinfunction "DAC0_32") (pintype "input+no_connect"))
    )
    (net (code "135") (name "unconnected-(Teensy 3.5-DAC1-Pad33)") (class "Default")
      (node (ref "Teensy 3.5") (pin "33") (pinfunction "DAC1_33") (pintype "input+no_connect"))
    )
    (net (code "136") (name "unconnected-(Teensy 3.5-GPIO_2-Pad4)") (class "Default")
      (node (ref "Teensy 3.5") (pin "4") (pinfunction "GPIO_2_4") (pintype "bidirectional"))
    )
    (net (code "137") (name "unconnected-(Teensy 3.5-GPIO_12-Pad14)") (class "Default")
      (node (ref "Teensy 3.5") (pin "14") (pinfunction "GPIO_12_14") (pintype "bidirectional"))
    )
    (net (code "138") (name "unconnected-(Teensy 3.5-GPIO_26-Pad18)") (class "Default")
      (node (ref "Teensy 3.5") (pin "18") (pinfunction "GPIO_26_18") (pintype "bidirectional"))
    )
    (net (code "139") (name "unconnected-(Teensy 3.5-GPIO_27-Pad19)") (class "Default")
      (node (ref "Teensy 3.5") (pin "19") (pinfunction "GPIO_27_19") (pintype "bidirectional"))
    )
    (net (code "140") (name "unconnected-(Teensy 3.5-GPIO_28-Pad20)") (class "Default")
      (node (ref "Teensy 3.5") (pin "20") (pinfunction "GPIO_28_20") (pintype "bidirectional"))
    )
    (net (code "141") (name "unconnected-(Teensy 3.5-GPIO_29-Pad21)") (class "Default")
      (node (ref "Teensy 3.5") (pin "21") (pinfunction "GPIO_29_21") (pintype "bidirectional"))
    )
    (net (code "142") (name "unconnected-(Teensy 3.5-GPIO_30-Pad22)") (class "Default")
      (node (ref "Teensy 3.5") (pin "22") (pinfunction "GPIO_30_22") (pintype "bidirectional"))
    )
    (net (code "143") (name "unconnected-(XBEE-PadMP1)") (class "Default")
      (node (ref "XBEE") (pin "MP1") (pinfunction "MP1_MP1") (pintype "passive"))
    )
    (net (code "144") (name "unconnected-(XBEE-PadMP2)") (class "Default")
      (node (ref "XBEE") (pin "MP2") (pinfunction "MP2_MP2") (pintype "passive"))
    )
  )
)
